# Power_Supply.net
KiCad netlist of a schematic drawn in Altium Designer
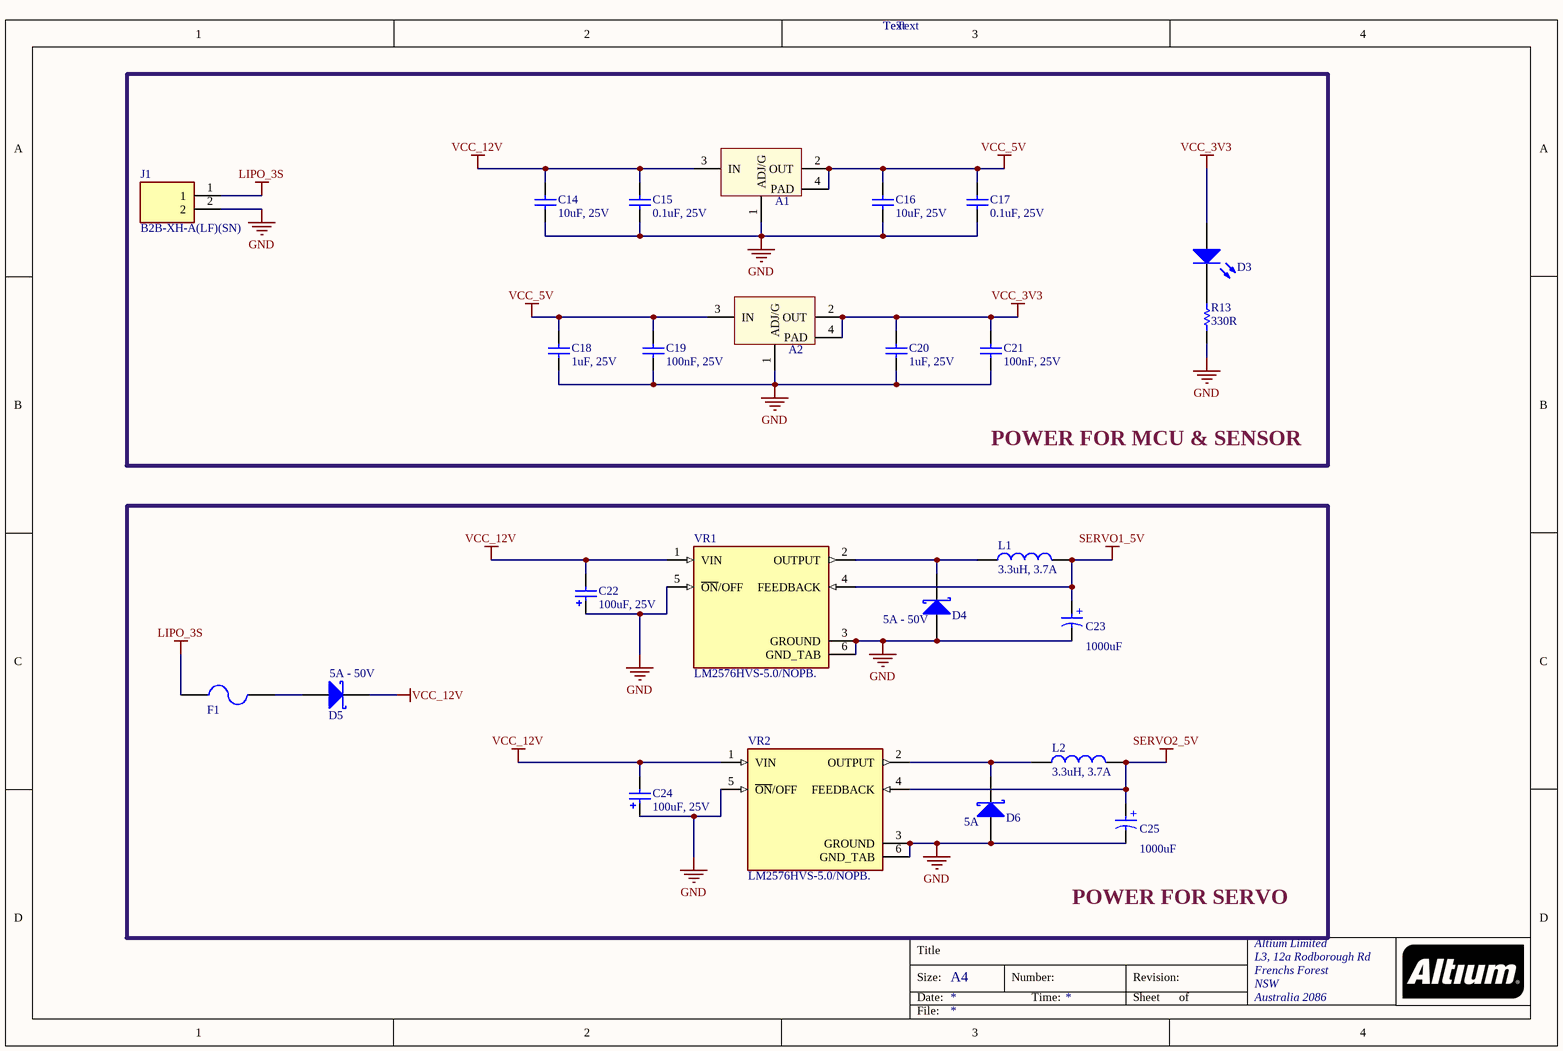
[diagram p0: Power_Supply.SchDoc]

(export (version "E")
  (design (tool "Eeschema 10.0.6"))
  (components
    (comp (ref "A1")
      (value "LM1117")
      (footprint "SOT223-4N")
      (description "Available in 1.8V, 2.5V, 2.85V, 3.3V, 5V, and  Adjustable Versions")
      (libsource (lib "PIF_Library") (part "LM1117"))
    )
    (comp (ref "A2")
      (value "LM1117")
      (footprint "SOT223-4N")
      (description "Available in 1.8V, 2.5V, 2.85V, 3.3V, 5V, and  Adjustable Versions")
      (libsource (lib "PIF_Library") (part "LM1117"))
    )
    (comp (ref "C14")
      (value "10uF, 25V")
      (footprint "CAP-SM-0805")
      (description "Capacitor")
      (fields (field (name "Comment") "Cap Non-Pol SMD"))
      (libsource (lib "PIF_Library") (part "Cap Non-Pol SMD"))
    )
    (comp (ref "C15")
      (value "0.1uF, 25V")
      (footprint "CAP-SM-0805")
      (description "Capacitor")
      (fields (field (name "Comment") "Cap Non-Pol SMD"))
      (libsource (lib "PIF_Library") (part "Cap Non-Pol SMD"))
    )
    (comp (ref "C16")
      (value "10uF, 25V")
      (footprint "CAP-SM-0805")
      (description "Capacitor")
      (fields (field (name "Comment") "Cap Non-Pol SMD"))
      (libsource (lib "PIF_Library") (part "Cap Non-Pol SMD"))
    )
    (comp (ref "C17")
      (value "0.1uF, 25V")
      (footprint "CAP-SM-0805")
      (description "Capacitor")
      (fields (field (name "Comment") "Cap Non-Pol SMD"))
      (libsource (lib "PIF_Library") (part "Cap Non-Pol SMD"))
    )
    (comp (ref "C18")
      (value "1uF, 25V")
      (footprint "CAP-SM-0805")
      (description "Capacitor")
      (fields (field (name "Comment") "Cap Non-Pol SMD"))
      (libsource (lib "PIF_Library") (part "Cap Non-Pol SMD"))
    )
    (comp (ref "C19")
      (value "100nF, 25V")
      (footprint "CAP-SM-0805")
      (description "Capacitor")
      (fields (field (name "Comment") "Cap Non-Pol SMD"))
      (libsource (lib "PIF_Library") (part "Cap Non-Pol SMD"))
    )
    (comp (ref "C20")
      (value "1uF, 25V")
      (footprint "CAP-SM-0805")
      (description "Capacitor")
      (fields (field (name "Comment") "Cap Non-Pol SMD"))
      (libsource (lib "PIF_Library") (part "Cap Non-Pol SMD"))
    )
    (comp (ref "C21")
      (value "100nF, 25V")
      (footprint "CAP-SM-0805")
      (description "Capacitor")
      (fields (field (name "Comment") "Cap Non-Pol SMD"))
      (libsource (lib "PIF_Library") (part "Cap Non-Pol SMD"))
    )
    (comp (ref "C22")
      (value "100uF, 25V")
      (footprint "CAP ALU SIZE F")
      (description "Polarized Capacitor (Radial)")
      (fields (field (name "Comment") "Cap Pol SMD"))
      (libsource (lib "PIF_Library") (part "Cap Pol SMD"))
    )
    (comp (ref "C23")
      (value "1000uF")
      (footprint "WCAP-ASLI_D12.5H14")
      (description "WCAP-ASLI Aluminum Electrolytic Capacitor, V-Chip, D12.5 x H14mm, 1000uF, 25V")
      (fields
        (field (name "MANUFACTURER PART NUMBER") "865080462016")
        (field (name "MANUFACTURER") "Wurth Elektronik")
      )
      (libsource (lib "Altium_WCAP-ASLI (rev22d)") (part "865080462016"))
    )
    (comp (ref "C24")
      (value "100uF, 25V")
      (footprint "CAP ALU SIZE F")
      (description "Polarized Capacitor (Radial)")
      (fields (field (name "Comment") "Cap Pol SMD"))
      (libsource (lib "PIF_Library") (part "Cap Pol SMD"))
    )
    (comp (ref "C25")
      (value "1000uF")
      (footprint "WCAP-ASLI_D12.5H14")
      (description "WCAP-ASLI Aluminum Electrolytic Capacitor, V-Chip, D12.5 x H14mm, 1000uF, 25V")
      (fields
        (field (name "MANUFACTURER PART NUMBER") "865080462016")
        (field (name "MANUFACTURER") "Wurth Elektronik")
      )
      (libsource (lib "Altium_WCAP-ASLI (rev22d)") (part "865080462016"))
    )
    (comp (ref "D3")
      (value "LED SMD")
      (footprint "LED_0603_Blue")
      (description "LED")
      (libsource (lib "PIF_Library") (part "LED SMD"))
    )
    (comp (ref "D4")
      (value "D Schottky")
      (footprint "SS34")
      (description "Schottky Diode")
      (fields (field (name "PUBLISHER") "Altium Limited"))
      (libsource (lib "PIF_Library") (part "D Schottky"))
    )
    (comp (ref "D5")
      (value "D Schottky")
      (footprint "SS34")
      (description "Schottky Diode")
      (fields (field (name "PUBLISHER") "Altium Limited"))
      (libsource (lib "PIF_Library") (part "D Schottky"))
    )
    (comp (ref "D6")
      (value "D Schottky")
      (footprint "SS34")
      (description "Schottky Diode")
      (fields (field (name "PUBLISHER") "Altium Limited"))
      (libsource (lib "PIF_Library") (part "D Schottky"))
    )
    (comp (ref "F1") (value "Fuse") (footprint "FUSE SMD") (libsource (lib "PIF_Library") (part "Fuse")))
    (comp (ref "J1")
      (value "B2B-XH-A(LF)(SN)")
      (footprint "JST_B2B-XH-A(LF)(SN)")
      (description "Connector Header Through Hole 2 position 0.098 (2.50mm)")
      (fields (field (name "MF") "JST Sales"))
      (libsource (lib "B2B-XH-A_LF__SN_") (part "B2B-XH-A(LF)(SN)"))
    )
    (comp (ref "L1")
      (value "3.3uH, 3.7A")
      (footprint "WE-PD2A_5848")
      (description "WE-PD2A SMT Power Inductor, size 5848, 3.3uH, 3.7A")
      (fields
        (field (name "MANUFACTURER PART NUMBER") "784774033")
        (field (name "MANUFACTURER") "Wurth Elektronik")
      )
      (libsource (lib "Altium_WE-PD2A (rev20a)") (part "784774033"))
    )
    (comp (ref "L2")
      (value "3.3uH, 3.7A")
      (footprint "WE-PD2A_5848")
      (description "WE-PD2A SMT Power Inductor, size 5848, 3.3uH, 3.7A")
      (fields
        (field (name "MANUFACTURER PART NUMBER") "784774033")
        (field (name "MANUFACTURER") "Wurth Elektronik")
      )
      (libsource (lib "Altium_WE-PD2A (rev20a)") (part "784774033"))
    )
    (comp (ref "R13")
      (value "330R")
      (footprint "RES-SM-0805")
      (description "Resistor")
      (fields (field (name "Comment") "RESISTOR SMD"))
      (libsource (lib "PIF_Library") (part "RESISTOR SMD"))
    )
    (comp (ref "VR1")
      (value "LM2576HVS-5.0/NOPB.")
      (footprint "TO170P1524X483-6N")
      (description "SIMPLE SWITCHER&reg; 4.5V to 40V, 3A Low Component Count Step-Down Regulator")
      (fields (field (name "MP") "LM2596S-5.0/NOPB") (field (name "MF") "Texas Instruments"))
      (libsource (lib "LM2596S-5.0") (part "LM2596S-5.0"))
    )
    (comp (ref "VR2")
      (value "LM2576HVS-5.0/NOPB.")
      (footprint "TO170P1524X483-6N")
      (description "SIMPLE SWITCHER&reg; 4.5V to 40V, 3A Low Component Count Step-Down Regulator")
      (fields (field (name "MP") "LM2596S-5.0/NOPB") (field (name "MF") "Texas Instruments"))
      (libsource (lib "LM2596S-5.0") (part "LM2596S-5.0"))
    )
  )
  (nets
    (net (code "1") (name "GND") (class "Default")
      (node (ref "A1") (pin "1") (pinfunction "ADJ/G_1") (pintype "passive"))
      (node (ref "A2") (pin "1") (pinfunction "ADJ/G_1") (pintype "passive"))
      (node (ref "C14") (pin "1") (pinfunction "1_1") (pintype "passive"))
      (node (ref "C15") (pin "1") (pinfunction "1_1") (pintype "passive"))
      (node (ref "C16") (pin "1") (pinfunction "1_1") (pintype "passive"))
      (node (ref "C17") (pin "1") (pinfunction "1_1") (pintype "passive"))
      (node (ref "C18") (pin "1") (pinfunction "1_1") (pintype "passive"))
      (node (ref "C19") (pin "1") (pinfunction "1_1") (pintype "passive"))
      (node (ref "C20") (pin "1") (pinfunction "1_1") (pintype "passive"))
      (node (ref "C21") (pin "1") (pinfunction "1_1") (pintype "passive"))
      (node (ref "C22") (pin "1") (pinfunction "1_1") (pintype "passive"))
      (node (ref "C23") (pin "2") (pinfunction "N_2") (pintype "passive"))
      (node (ref "C24") (pin "1") (pinfunction "1_1") (pintype "passive"))
      (node (ref "C25") (pin "2") (pinfunction "N_2") (pintype "passive"))
      (node (ref "D4") (pin "1") (pinfunction "A_1") (pintype "passive"))
      (node (ref "D6") (pin "1") (pinfunction "A_1") (pintype "passive"))
      (node (ref "J1") (pin "2") (pinfunction "2_2") (pintype "passive"))
      (node (ref "R13") (pin "2") (pinfunction "2_2") (pintype "passive"))
      (node (ref "VR1") (pin "3") (pinfunction "GROUND_3") (pintype "power_in"))
      (node (ref "VR1") (pin "5") (pinfunction "~{ON}/OFF_5") (pintype "input"))
      (node (ref "VR1") (pin "6") (pinfunction "GND_TAB_6") (pintype "power_in"))
      (node (ref "VR2") (pin "3") (pinfunction "GROUND_3") (pintype "power_in"))
      (node (ref "VR2") (pin "5") (pinfunction "~{ON}/OFF_5") (pintype "input"))
      (node (ref "VR2") (pin "6") (pinfunction "GND_TAB_6") (pintype "power_in"))
    )
    (net (code "2") (name "LIPO_3S") (class "Default")
      (node (ref "F1") (pin "1") (pinfunction "1_1") (pintype "passive"))
      (node (ref "J1") (pin "1") (pinfunction "1_1") (pintype "passive"))
    )
    (net (code "3") (name "Net-(D3-K)") (class "Default")
      (node (ref "D3") (pin "2") (pinfunction "K_2") (pintype "passive"))
      (node (ref "R13") (pin "1") (pinfunction "1_1") (pintype "passive"))
    )
    (net (code "4") (name "Net-(D4-K)") (class "Default")
      (node (ref "D4") (pin "2") (pinfunction "K_2") (pintype "passive"))
      (node (ref "L1") (pin "1") (pinfunction "1_1") (pintype "passive"))
      (node (ref "VR1") (pin "2") (pinfunction "OUTPUT_2") (pintype "output"))
    )
    (net (code "5") (name "Net-(D5-A)") (class "Default")
      (node (ref "D5") (pin "1") (pinfunction "A_1") (pintype "passive"))
      (node (ref "F1") (pin "2") (pinfunction "2_2") (pintype "passive"))
    )
    (net (code "6") (name "Net-(D6-K)") (class "Default")
      (node (ref "D6") (pin "2") (pinfunction "K_2") (pintype "passive"))
      (node (ref "L2") (pin "1") (pinfunction "1_1") (pintype "passive"))
      (node (ref "VR2") (pin "2") (pinfunction "OUTPUT_2") (pintype "output"))
    )
    (net (code "7") (name "SERVO1_5V") (class "Default")
      (node (ref "C23") (pin "1") (pinfunction "P_1") (pintype "passive"))
      (node (ref "L1") (pin "2") (pinfunction "2_2") (pintype "passive"))
      (node (ref "VR1") (pin "4") (pinfunction "FEEDBACK_4") (pintype "input"))
    )
    (net (code "8") (name "SERVO2_5V") (class "Default")
      (node (ref "C25") (pin "1") (pinfunction "P_1") (pintype "passive"))
      (node (ref "L2") (pin "2") (pinfunction "2_2") (pintype "passive"))
      (node (ref "VR2") (pin "4") (pinfunction "FEEDBACK_4") (pintype "input"))
    )
    (net (code "9") (name "VCC_3V3") (class "Default")
      (node (ref "A2") (pin "2") (pinfunction "OUT_2") (pintype "passive"))
      (node (ref "A2") (pin "4") (pinfunction "PAD_4") (pintype "passive"))
      (node (ref "C20") (pin "2") (pinfunction "2_2") (pintype "passive"))
      (node (ref "C21") (pin "2") (pinfunction "2_2") (pintype "passive"))
      (node (ref "D3") (pin "1") (pinfunction "A_1") (pintype "passive"))
    )
    (net (code "10") (name "VCC_5V") (class "Default")
      (node (ref "A1") (pin "2") (pinfunction "OUT_2") (pintype "passive"))
      (node (ref "A1") (pin "4") (pinfunction "PAD_4") (pintype "passive"))
      (node (ref "A2") (pin "3") (pinfunction "IN_3") (pintype "passive"))
      (node (ref "C16") (pin "2") (pinfunction "2_2") (pintype "passive"))
      (node (ref "C17") (pin "2") (pinfunction "2_2") (pintype "passive"))
      (node (ref "C18") (pin "2") (pinfunction "2_2") (pintype "passive"))
      (node (ref "C19") (pin "2") (pinfunction "2_2") (pintype "passive"))
    )
    (net (code "11") (name "VCC_12V") (class "Default")
      (node (ref "A1") (pin "3") (pinfunction "IN_3") (pintype "passive"))
      (node (ref "C14") (pin "2") (pinfunction "2_2") (pintype "passive"))
      (node (ref "C15") (pin "2") (pinfunction "2_2") (pintype "passive"))
      (node (ref "C22") (pin "2") (pinfunction "2_2") (pintype "passive"))
      (node (ref "C24") (pin "2") (pinfunction "2_2") (pintype "passive"))
      (node (ref "D5") (pin "2") (pinfunction "K_2") (pintype "passive"))
      (node (ref "VR1") (pin "1") (pinfunction "VIN_1") (pintype "input"))
      (node (ref "VR2") (pin "1") (pinfunction "VIN_1") (pintype "input"))
    )
  )
)
